# 2017MXP_board.net
KiCad netlist of a schematic drawn in EAGLE
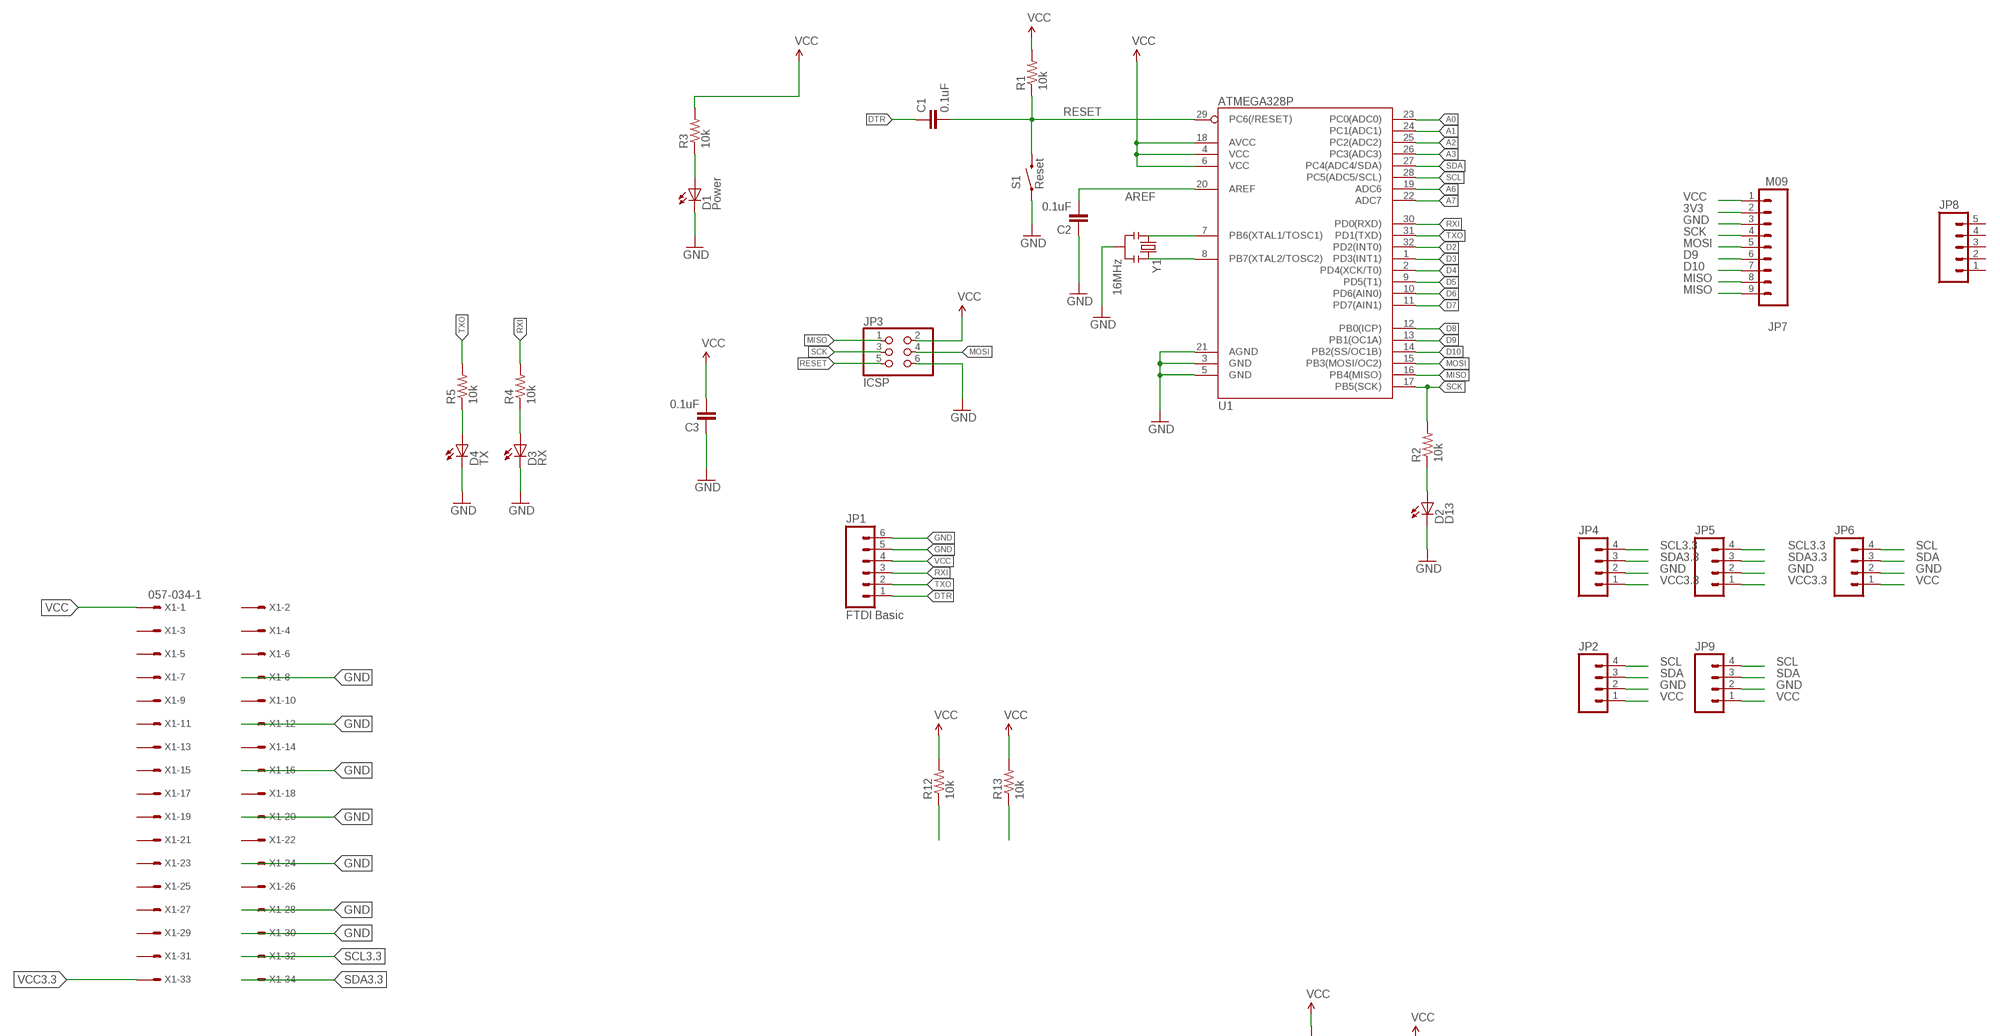
[diagram p0: schematic, sheet 1, part 1 of 2]
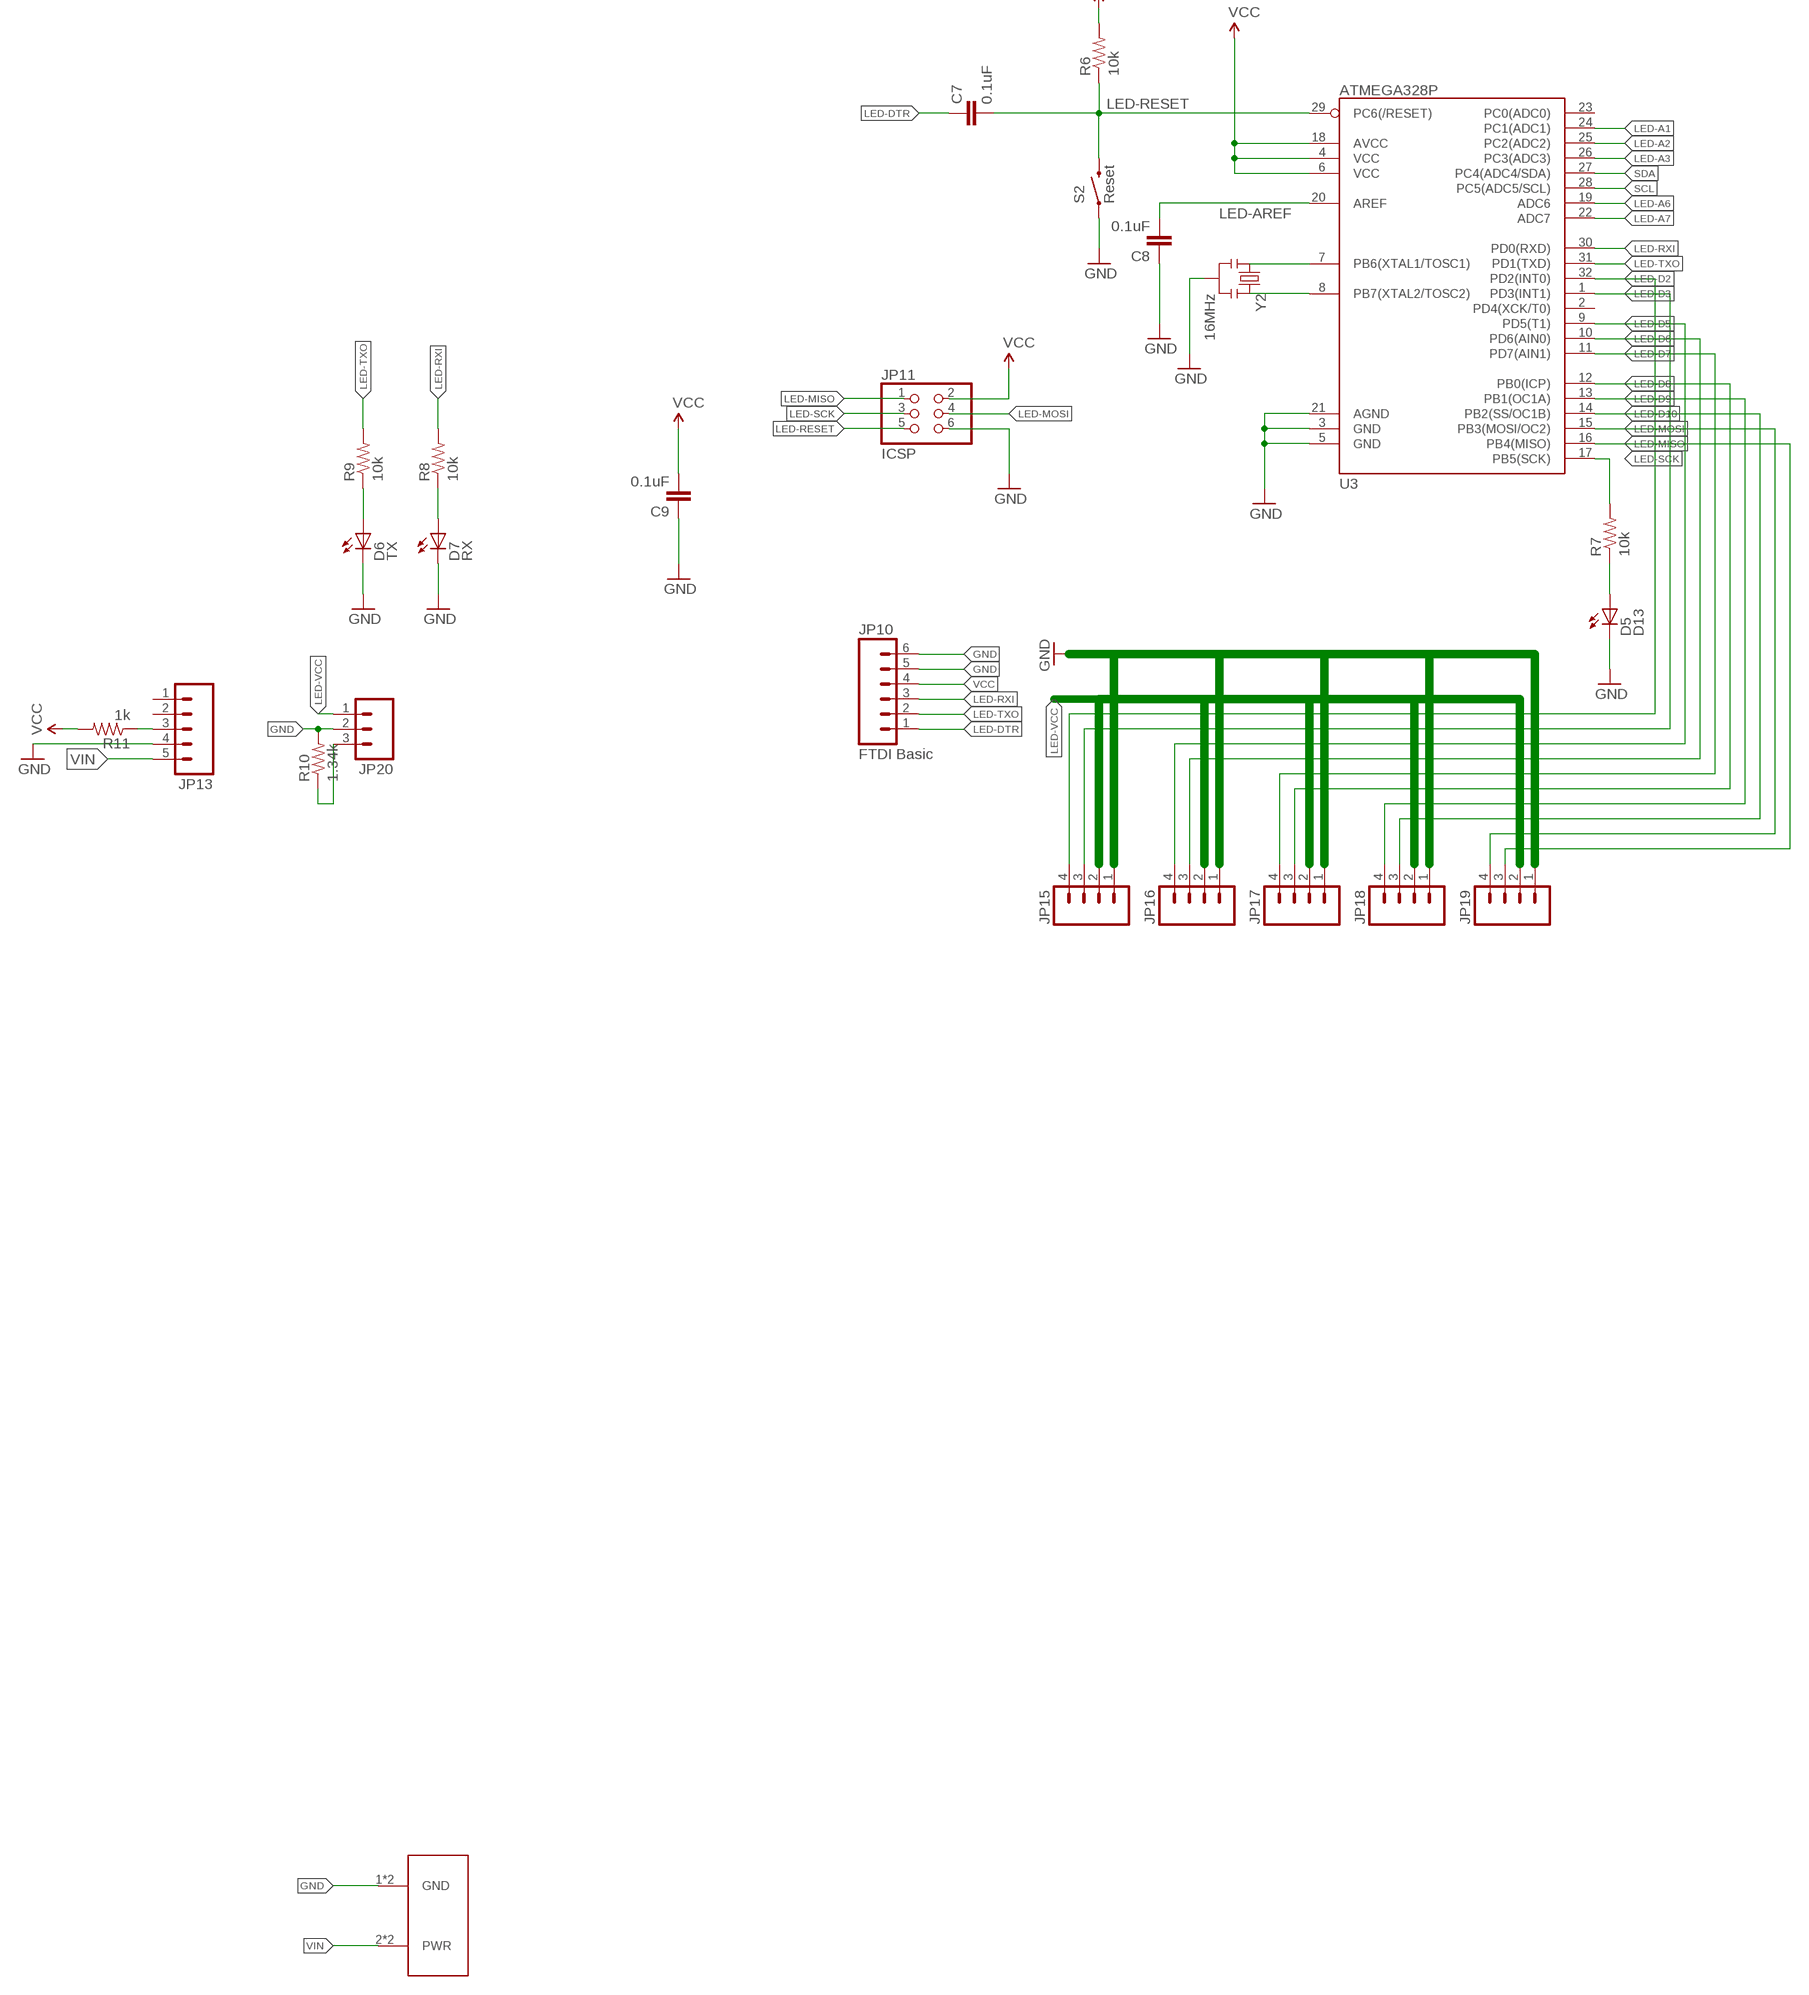
[diagram p1: schematic, sheet 1, part 2 of 2]

(export (version "E")
  (design (tool "Eeschema 10.0.6"))
  (components
    (comp (ref "C1")
      (value "0.1uF")
      (footprint "eagle-import:0603-CAP")
      (libsource (lib "eagle-import") (part "CAP0603-CAP"))
    )
    (comp (ref "C2")
      (value "0.1uF")
      (footprint "eagle-import:0603-CAP")
      (libsource (lib "eagle-import") (part "CAP0603-CAP"))
    )
    (comp (ref "C3")
      (value "0.1uF")
      (footprint "eagle-import:0603-CAP")
      (libsource (lib "eagle-import") (part "CAP0603-CAP"))
    )
    (comp (ref "C7")
      (value "0.1uF")
      (footprint "eagle-import:0603-CAP")
      (libsource (lib "eagle-import") (part "CAP0603-CAP"))
    )
    (comp (ref "C8")
      (value "0.1uF")
      (footprint "eagle-import:0603-CAP")
      (libsource (lib "eagle-import") (part "CAP0603-CAP"))
    )
    (comp (ref "C9")
      (value "0.1uF")
      (footprint "eagle-import:0603-CAP")
      (libsource (lib "eagle-import") (part "CAP0603-CAP"))
    )
    (comp (ref "D1")
      (value "Power")
      (footprint "eagle-import:LED-0603")
      (libsource (lib "eagle-import") (part "LED-RED0603"))
    )
    (comp (ref "D2")
      (value "D13")
      (footprint "eagle-import:LED-0603")
      (libsource (lib "eagle-import") (part "LED-RED0603"))
    )
    (comp (ref "D3")
      (value "RX")
      (footprint "eagle-import:LED-0603")
      (libsource (lib "eagle-import") (part "LED-GREEN0603"))
    )
    (comp (ref "D4")
      (value "TX")
      (footprint "eagle-import:LED-0603")
      (libsource (lib "eagle-import") (part "LED-RED0603"))
    )
    (comp (ref "D5")
      (value "D13")
      (footprint "eagle-import:LED-0603")
      (libsource (lib "eagle-import") (part "LED-RED0603"))
    )
    (comp (ref "D6")
      (value "TX")
      (footprint "eagle-import:LED-0603")
      (libsource (lib "eagle-import") (part "LED-RED0603"))
    )
    (comp (ref "D7")
      (value "RX")
      (footprint "eagle-import:LED-0603")
      (libsource (lib "eagle-import") (part "LED-GREEN0603"))
    )
    (comp (ref "JP1")
      (value "FTDI Basic")
      (footprint "eagle-import:1X06")
      (libsource (lib "eagle-import") (part "M06SIP"))
    )
    (comp (ref "JP2")
      (value "M04PTH")
      (footprint "eagle-import:1X04")
      (libsource (lib "eagle-import") (part "M04PTH"))
    )
    (comp (ref "JP3")
      (value "ICSP")
      (footprint "eagle-import:2X03")
      (libsource (lib "eagle-import") (part "PINHD-2X3"))
    )
    (comp (ref "JP4")
      (value "M04PTH")
      (footprint "eagle-import:1X04")
      (libsource (lib "eagle-import") (part "M04PTH"))
    )
    (comp (ref "JP5")
      (value "M04PTH")
      (footprint "eagle-import:1X04")
      (libsource (lib "eagle-import") (part "M04PTH"))
    )
    (comp (ref "JP6")
      (value "M04PTH")
      (footprint "eagle-import:1X04")
      (libsource (lib "eagle-import") (part "M04PTH"))
    )
    (comp (ref "JP7")
      (value "M09")
      (footprint "eagle-import:1X09")
      (libsource (lib "eagle-import") (part "M09"))
    )
    (comp (ref "JP8")
      (value "M05PTH")
      (footprint "eagle-import:1X05")
      (libsource (lib "eagle-import") (part "M05PTH"))
    )
    (comp (ref "JP9")
      (value "M04PTH")
      (footprint "eagle-import:1X04")
      (libsource (lib "eagle-import") (part "M04PTH"))
    )
    (comp (ref "JP10")
      (value "FTDI Basic")
      (footprint "eagle-import:1X06")
      (libsource (lib "eagle-import") (part "M06SIP"))
    )
    (comp (ref "JP11")
      (value "ICSP")
      (footprint "eagle-import:2X03")
      (libsource (lib "eagle-import") (part "PINHD-2X3"))
    )
    (comp (ref "JP13")
      (value "M05PTH")
      (footprint "eagle-import:1X05")
      (libsource (lib "eagle-import") (part "M05PTH"))
    )
    (comp (ref "JP15")
      (value "M04PTH")
      (footprint "eagle-import:1X04")
      (libsource (lib "eagle-import") (part "M04PTH"))
    )
    (comp (ref "JP16")
      (value "M04PTH")
      (footprint "eagle-import:1X04")
      (libsource (lib "eagle-import") (part "M04PTH"))
    )
    (comp (ref "JP17")
      (value "M04PTH")
      (footprint "eagle-import:1X04")
      (libsource (lib "eagle-import") (part "M04PTH"))
    )
    (comp (ref "JP18")
      (value "M04PTH")
      (footprint "eagle-import:1X04")
      (libsource (lib "eagle-import") (part "M04PTH"))
    )
    (comp (ref "JP19")
      (value "M04PTH")
      (footprint "eagle-import:1X04")
      (libsource (lib "eagle-import") (part "M04PTH"))
    )
    (comp (ref "JP20")
      (value "M03PTH")
      (footprint "eagle-import:1X03")
      (libsource (lib "eagle-import") (part "M03PTH"))
    )
    (comp (ref "R1")
      (value "10k")
      (footprint "eagle-import:0603-RES")
      (libsource (lib "eagle-import") (part "RESISTOR0603-RES"))
    )
    (comp (ref "R2")
      (value "10k")
      (footprint "eagle-import:0603-RES")
      (libsource (lib "eagle-import") (part "RESISTOR0603-RES"))
    )
    (comp (ref "R3")
      (value "10k")
      (footprint "eagle-import:0603-RES")
      (libsource (lib "eagle-import") (part "RESISTOR0603-RES"))
    )
    (comp (ref "R4")
      (value "10k")
      (footprint "eagle-import:0603-RES")
      (libsource (lib "eagle-import") (part "RESISTOR0603-RES"))
    )
    (comp (ref "R5")
      (value "10k")
      (footprint "eagle-import:0603-RES")
      (libsource (lib "eagle-import") (part "RESISTOR0603-RES"))
    )
    (comp (ref "R6")
      (value "10k")
      (footprint "eagle-import:0603-RES")
      (libsource (lib "eagle-import") (part "RESISTOR0603-RES"))
    )
    (comp (ref "R7")
      (value "10k")
      (footprint "eagle-import:0603-RES")
      (libsource (lib "eagle-import") (part "RESISTOR0603-RES"))
    )
    (comp (ref "R8")
      (value "10k")
      (footprint "eagle-import:0603-RES")
      (libsource (lib "eagle-import") (part "RESISTOR0603-RES"))
    )
    (comp (ref "R9")
      (value "10k")
      (footprint "eagle-import:0603-RES")
      (libsource (lib "eagle-import") (part "RESISTOR0603-RES"))
    )
    (comp (ref "R10")
      (value "1.34k")
      (footprint "eagle-import:AXIAL-0.3")
      (libsource (lib "eagle-import") (part "SparkFun-Resistors_RESISTORAXIAL-0.3"))
    )
    (comp (ref "R11")
      (value "1k")
      (footprint "eagle-import:AXIAL-0.3")
      (libsource (lib "eagle-import") (part "SparkFun-Resistors_RESISTORAXIAL-0.3"))
    )
    (comp (ref "R12")
      (value "10k")
      (footprint "eagle-import:0603-RES")
      (libsource (lib "eagle-import") (part "RESISTOR0603-RES"))
    )
    (comp (ref "R13")
      (value "10k")
      (footprint "eagle-import:0603-RES")
      (libsource (lib "eagle-import") (part "RESISTOR0603-RES"))
    )
    (comp (ref "S1")
      (value "Reset")
      (footprint "eagle-import:TACTILE_SWITCH_SMD")
      (libsource (lib "eagle-import") (part "SWITCH-MOMENTARY-2SMD"))
    )
    (comp (ref "S2")
      (value "Reset")
      (footprint "eagle-import:TACTILE_SWITCH_SMD")
      (libsource (lib "eagle-import") (part "SWITCH-MOMENTARY-2SMD"))
    )
    (comp (ref "U$2")
      (value "LSF-SMT")
      (footprint "eagle-import:LSF-SMT")
      (libsource (lib "eagle-import") (part "LSF-SMT"))
    )
    (comp (ref "U1")
      (value "ATMEGA328P")
      (footprint "eagle-import:TQFP32-08")
      (libsource (lib "eagle-import") (part "ATMEGA328_SMT"))
    )
    (comp (ref "U3")
      (value "ATMEGA328P")
      (footprint "eagle-import:TQFP32-08")
      (libsource (lib "eagle-import") (part "ATMEGA328_SMT"))
    )
    (comp (ref "X1")
      (value "057-034-1")
      (footprint "eagle-import:057-034-1")
      (libsource (lib "eagle-import") (part "057-034-1"))
    )
    (comp (ref "Y1")
      (value "16MHz")
      (footprint "eagle-import:RESONATOR-SMD")
      (libsource (lib "eagle-import") (part "RESONATOR16MHZ"))
    )
    (comp (ref "Y2")
      (value "16MHz")
      (footprint "eagle-import:RESONATOR-SMD")
      (libsource (lib "eagle-import") (part "RESONATOR16MHZ"))
    )
  )
  (nets
    (net (code "1") (name "/3V3") (class "Default")
      (node (ref "JP7") (pin "2") (pinfunction "2_2") (pintype "passive"))
    )
    (net (code "2") (name "/AREF") (class "Default")
      (node (ref "C2") (pin "2") (pinfunction "2_2") (pintype "passive"))
      (node (ref "U1") (pin "20") (pinfunction "AREF_20") (pintype "bidirectional"))
    )
    (net (code "3") (name "/LED-AREF") (class "Default")
      (node (ref "C8") (pin "2") (pinfunction "2_2") (pintype "passive"))
      (node (ref "U3") (pin "20") (pinfunction "AREF_20") (pintype "bidirectional"))
    )
    (net (code "4") (name "A0") (class "Default")
      (node (ref "U1") (pin "23") (pinfunction "PC0(ADC0)_23") (pintype "bidirectional"))
    )
    (net (code "5") (name "A1") (class "Default")
      (node (ref "U1") (pin "24") (pinfunction "PC1(ADC1)_24") (pintype "bidirectional"))
    )
    (net (code "6") (name "A2") (class "Default")
      (node (ref "U1") (pin "25") (pinfunction "PC2(ADC2)_25") (pintype "bidirectional"))
    )
    (net (code "7") (name "A3") (class "Default")
      (node (ref "U1") (pin "26") (pinfunction "PC3(ADC3)_26") (pintype "bidirectional"))
    )
    (net (code "8") (name "A6") (class "Default")
      (node (ref "U1") (pin "19") (pinfunction "ADC6_19") (pintype "bidirectional"))
    )
    (net (code "9") (name "A7") (class "Default")
      (node (ref "U1") (pin "22") (pinfunction "ADC7_22") (pintype "bidirectional"))
    )
    (net (code "10") (name "D2") (class "Default")
      (node (ref "U1") (pin "32") (pinfunction "PD2(INT0)_32") (pintype "bidirectional"))
    )
    (net (code "11") (name "D3") (class "Default")
      (node (ref "U1") (pin "1") (pinfunction "PD3(INT1)_1") (pintype "bidirectional"))
    )
    (net (code "12") (name "D4") (class "Default")
      (node (ref "U1") (pin "2") (pinfunction "PD4(XCK/T0)_2") (pintype "bidirectional"))
    )
    (net (code "13") (name "D5") (class "Default")
      (node (ref "U1") (pin "9") (pinfunction "PD5(T1)_9") (pintype "bidirectional"))
    )
    (net (code "14") (name "D6") (class "Default")
      (node (ref "U1") (pin "10") (pinfunction "PD6(AIN0)_10") (pintype "bidirectional"))
    )
    (net (code "15") (name "D7") (class "Default")
      (node (ref "U1") (pin "11") (pinfunction "PD7(AIN1)_11") (pintype "bidirectional"))
    )
    (net (code "16") (name "D8") (class "Default")
      (node (ref "U1") (pin "12") (pinfunction "PB0(ICP)_12") (pintype "bidirectional"))
    )
    (net (code "17") (name "D9") (class "Default")
      (node (ref "JP7") (pin "6") (pinfunction "6_6") (pintype "passive"))
      (node (ref "U1") (pin "13") (pinfunction "PB1(OC1A)_13") (pintype "bidirectional"))
    )
    (net (code "18") (name "D10") (class "Default")
      (node (ref "JP7") (pin "7") (pinfunction "7_7") (pintype "passive"))
      (node (ref "U1") (pin "14") (pinfunction "PB2(SS/OC1B)_14") (pintype "bidirectional"))
    )
    (net (code "19") (name "DTR") (class "Default")
      (node (ref "C1") (pin "1") (pinfunction "1_1") (pintype "passive"))
      (node (ref "JP1") (pin "1") (pinfunction "1_1") (pintype "passive"))
    )
    (net (code "20") (name "GND") (class "Default")
      (node (ref "C2") (pin "1") (pinfunction "1_1") (pintype "passive"))
      (node (ref "C3") (pin "1") (pinfunction "1_1") (pintype "passive"))
      (node (ref "C8") (pin "1") (pinfunction "1_1") (pintype "passive"))
      (node (ref "C9") (pin "1") (pinfunction "1_1") (pintype "passive"))
      (node (ref "D1") (pin "C") (pinfunction "C_C") (pintype "passive"))
      (node (ref "D2") (pin "C") (pinfunction "C_C") (pintype "passive"))
      (node (ref "D3") (pin "C") (pinfunction "C_C") (pintype "passive"))
      (node (ref "D4") (pin "C") (pinfunction "C_C") (pintype "passive"))
      (node (ref "D5") (pin "C") (pinfunction "C_C") (pintype "passive"))
      (node (ref "D6") (pin "C") (pinfunction "C_C") (pintype "passive"))
      (node (ref "D7") (pin "C") (pinfunction "C_C") (pintype "passive"))
      (node (ref "JP1") (pin "5") (pinfunction "5_5") (pintype "passive"))
      (node (ref "JP1") (pin "6") (pinfunction "6_6") (pintype "passive"))
      (node (ref "JP10") (pin "5") (pinfunction "5_5") (pintype "passive"))
      (node (ref "JP10") (pin "6") (pinfunction "6_6") (pintype "passive"))
      (node (ref "JP11") (pin "6") (pinfunction "6_6") (pintype "passive"))
      (node (ref "JP13") (pin "4") (pinfunction "4_4") (pintype "passive"))
      (node (ref "JP15") (pin "1") (pinfunction "1_1") (pintype "passive"))
      (node (ref "JP16") (pin "1") (pinfunction "1_1") (pintype "passive"))
      (node (ref "JP17") (pin "1") (pinfunction "1_1") (pintype "passive"))
      (node (ref "JP18") (pin "1") (pinfunction "1_1") (pintype "passive"))
      (node (ref "JP19") (pin "1") (pinfunction "1_1") (pintype "passive"))
      (node (ref "JP2") (pin "2") (pinfunction "2_2") (pintype "passive"))
      (node (ref "JP20") (pin "2") (pinfunction "2_2") (pintype "passive"))
      (node (ref "JP3") (pin "6") (pinfunction "6_6") (pintype "passive"))
      (node (ref "JP4") (pin "2") (pinfunction "2_2") (pintype "passive"))
      (node (ref "JP5") (pin "2") (pinfunction "2_2") (pintype "passive"))
      (node (ref "JP6") (pin "2") (pinfunction "2_2") (pintype "passive"))
      (node (ref "JP7") (pin "3") (pinfunction "3_3") (pintype "passive"))
      (node (ref "JP9") (pin "2") (pinfunction "2_2") (pintype "passive"))
      (node (ref "R10") (pin "P$2") (pinfunction "2_P$2") (pintype "passive"))
      (node (ref "S1") (pin "1") (pinfunction "1_1") (pintype "passive"))
      (node (ref "S2") (pin "1") (pinfunction "1_1") (pintype "passive"))
      (node (ref "U$2") (pin "1") (pinfunction "GND_1") (pintype "bidirectional"))
      (node (ref "U$2") (pin "1-2") (pinfunction "GND_1-2") (pintype "bidirectional"))
      (node (ref "U1") (pin "21") (pinfunction "AGND_21") (pintype "bidirectional"))
      (node (ref "U1") (pin "3") (pinfunction "GND_3") (pintype "bidirectional"))
      (node (ref "U1") (pin "5") (pinfunction "GND_5") (pintype "bidirectional"))
      (node (ref "U3") (pin "21") (pinfunction "AGND_21") (pintype "bidirectional"))
      (node (ref "U3") (pin "3") (pinfunction "GND_3") (pintype "bidirectional"))
      (node (ref "U3") (pin "5") (pinfunction "GND_5") (pintype "bidirectional"))
      (node (ref "X1") (pin "12") (pinfunction "S_12") (pintype "passive"))
      (node (ref "X1") (pin "16") (pinfunction "S_16") (pintype "passive"))
      (node (ref "X1") (pin "20") (pinfunction "S_20") (pintype "passive"))
      (node (ref "X1") (pin "24") (pinfunction "S_24") (pintype "passive"))
      (node (ref "X1") (pin "28") (pinfunction "S_28") (pintype "passive"))
      (node (ref "X1") (pin "30") (pinfunction "S_30") (pintype "passive"))
      (node (ref "X1") (pin "8") (pinfunction "S_8") (pintype "passive"))
      (node (ref "Y1") (pin "2") (pinfunction "2_2") (pintype "passive"))
      (node (ref "Y2") (pin "2") (pinfunction "2_2") (pintype "passive"))
    )
    (net (code "21") (name "LED-A1") (class "Default")
      (node (ref "U3") (pin "24") (pinfunction "PC1(ADC1)_24") (pintype "bidirectional"))
    )
    (net (code "22") (name "LED-A2") (class "Default")
      (node (ref "U3") (pin "25") (pinfunction "PC2(ADC2)_25") (pintype "bidirectional"))
    )
    (net (code "23") (name "LED-A3") (class "Default")
      (node (ref "U3") (pin "26") (pinfunction "PC3(ADC3)_26") (pintype "bidirectional"))
    )
    (net (code "24") (name "LED-A6") (class "Default")
      (node (ref "U3") (pin "19") (pinfunction "ADC6_19") (pintype "bidirectional"))
    )
    (net (code "25") (name "LED-A7") (class "Default")
      (node (ref "U3") (pin "22") (pinfunction "ADC7_22") (pintype "bidirectional"))
    )
    (net (code "26") (name "LED-D2") (class "Default")
      (node (ref "JP15") (pin "4") (pinfunction "4_4") (pintype "passive"))
      (node (ref "U3") (pin "32") (pinfunction "PD2(INT0)_32") (pintype "bidirectional"))
    )
    (net (code "27") (name "LED-D3") (class "Default")
      (node (ref "JP15") (pin "3") (pinfunction "3_3") (pintype "passive"))
      (node (ref "U3") (pin "1") (pinfunction "PD3(INT1)_1") (pintype "bidirectional"))
    )
    (net (code "28") (name "LED-D5") (class "Default")
      (node (ref "JP16") (pin "4") (pinfunction "4_4") (pintype "passive"))
      (node (ref "U3") (pin "9") (pinfunction "PD5(T1)_9") (pintype "bidirectional"))
    )
    (net (code "29") (name "LED-D6") (class "Default")
      (node (ref "JP16") (pin "3") (pinfunction "3_3") (pintype "passive"))
      (node (ref "U3") (pin "10") (pinfunction "PD6(AIN0)_10") (pintype "bidirectional"))
    )
    (net (code "30") (name "LED-D7") (class "Default")
      (node (ref "JP17") (pin "4") (pinfunction "4_4") (pintype "passive"))
      (node (ref "U3") (pin "11") (pinfunction "PD7(AIN1)_11") (pintype "bidirectional"))
    )
    (net (code "31") (name "LED-D8") (class "Default")
      (node (ref "JP17") (pin "3") (pinfunction "3_3") (pintype "passive"))
      (node (ref "U3") (pin "12") (pinfunction "PB0(ICP)_12") (pintype "bidirectional"))
    )
    (net (code "32") (name "LED-D9") (class "Default")
      (node (ref "JP18") (pin "4") (pinfunction "4_4") (pintype "passive"))
      (node (ref "U3") (pin "13") (pinfunction "PB1(OC1A)_13") (pintype "bidirectional"))
    )
    (net (code "33") (name "LED-D10") (class "Default")
      (node (ref "JP18") (pin "3") (pinfunction "3_3") (pintype "passive"))
      (node (ref "U3") (pin "14") (pinfunction "PB2(SS/OC1B)_14") (pintype "bidirectional"))
    )
    (net (code "34") (name "LED-DTR") (class "Default")
      (node (ref "C7") (pin "1") (pinfunction "1_1") (pintype "passive"))
      (node (ref "JP10") (pin "1") (pinfunction "1_1") (pintype "passive"))
    )
    (net (code "35") (name "LED-MISO") (class "Default")
      (node (ref "JP11") (pin "1") (pinfunction "1_1") (pintype "passive"))
      (node (ref "JP19") (pin "3") (pinfunction "3_3") (pintype "passive"))
      (node (ref "U3") (pin "16") (pinfunction "PB4(MISO)_16") (pintype "bidirectional"))
    )
    (net (code "36") (name "LED-MOSI") (class "Default")
      (node (ref "JP11") (pin "4") (pinfunction "4_4") (pintype "passive"))
      (node (ref "JP19") (pin "4") (pinfunction "4_4") (pintype "passive"))
      (node (ref "U3") (pin "15") (pinfunction "PB3(MOSI/OC2)_15") (pintype "bidirectional"))
    )
    (net (code "37") (name "LED-RESET") (class "Default")
      (node (ref "C7") (pin "2") (pinfunction "2_2") (pintype "passive"))
      (node (ref "JP11") (pin "5") (pinfunction "5_5") (pintype "passive"))
      (node (ref "R6") (pin "1") (pinfunction "1_1") (pintype "passive"))
      (node (ref "S2") (pin "3") (pinfunction "2_3") (pintype "passive"))
      (node (ref "U3") (pin "29") (pinfunction "PC6(/RESET)_29") (pintype "bidirectional"))
    )
    (net (code "38") (name "LED-RXI") (class "Default")
      (node (ref "JP10") (pin "3") (pinfunction "3_3") (pintype "passive"))
      (node (ref "R8") (pin "2") (pinfunction "2_2") (pintype "passive"))
      (node (ref "U3") (pin "30") (pinfunction "PD0(RXD)_30") (pintype "bidirectional"))
    )
    (net (code "39") (name "LED-SCK") (class "Default")
      (node (ref "JP11") (pin "3") (pinfunction "3_3") (pintype "passive"))
      (node (ref "R7") (pin "2") (pinfunction "2_2") (pintype "passive"))
      (node (ref "U3") (pin "17") (pinfunction "PB5(SCK)_17") (pintype "bidirectional"))
    )
    (net (code "40") (name "LED-TXO") (class "Default")
      (node (ref "JP10") (pin "2") (pinfunction "2_2") (pintype "passive"))
      (node (ref "R9") (pin "2") (pinfunction "2_2") (pintype "passive"))
      (node (ref "U3") (pin "31") (pinfunction "PD1(TXD)_31") (pintype "bidirectional"))
    )
    (net (code "41") (name "LED-VCC") (class "Default")
      (node (ref "JP15") (pin "2") (pinfunction "2_2") (pintype "passive"))
      (node (ref "JP16") (pin "2") (pinfunction "2_2") (pintype "passive"))
      (node (ref "JP17") (pin "2") (pinfunction "2_2") (pintype "passive"))
      (node (ref "JP18") (pin "2") (pinfunction "2_2") (pintype "passive"))
      (node (ref "JP19") (pin "2") (pinfunction "2_2") (pintype "passive"))
      (node (ref "JP20") (pin "1") (pinfunction "1_1") (pintype "passive"))
    )
    (net (code "42") (name "MISO") (class "Default")
      (node (ref "JP3") (pin "1") (pinfunction "1_1") (pintype "passive"))
      (node (ref "JP7") (pin "8") (pinfunction "8_8") (pintype "passive"))
      (node (ref "JP7") (pin "9") (pinfunction "9_9") (pintype "passive"))
      (node (ref "U1") (pin "16") (pinfunction "PB4(MISO)_16") (pintype "bidirectional"))
    )
    (net (code "43") (name "MOSI") (class "Default")
      (node (ref "JP3") (pin "4") (pinfunction "4_4") (pintype "passive"))
      (node (ref "JP7") (pin "5") (pinfunction "5_5") (pintype "passive"))
      (node (ref "U1") (pin "15") (pinfunction "PB3(MOSI/OC2)_15") (pintype "bidirectional"))
    )
    (net (code "44") (name "Net-(D1-PadA)") (class "Default")
      (node (ref "D1") (pin "A") (pinfunction "A_A") (pintype "passive"))
      (node (ref "R3") (pin "1") (pinfunction "1_1") (pintype "passive"))
    )
    (net (code "45") (name "Net-(D2-PadA)") (class "Default")
      (node (ref "D2") (pin "A") (pinfunction "A_A") (pintype "passive"))
      (node (ref "R2") (pin "1") (pinfunction "1_1") (pintype "passive"))
    )
    (net (code "46") (name "Net-(D3-PadA)") (class "Default")
      (node (ref "D3") (pin "A") (pinfunction "A_A") (pintype "passive"))
      (node (ref "R4") (pin "1") (pinfunction "1_1") (pintype "passive"))
    )
    (net (code "47") (name "Net-(D4-PadA)") (class "Default")
      (node (ref "D4") (pin "A") (pinfunction "A_A") (pintype "passive"))
      (node (ref "R5") (pin "1") (pinfunction "1_1") (pintype "passive"))
    )
    (net (code "48") (name "Net-(D5-PadA)") (class "Default")
      (node (ref "D5") (pin "A") (pinfunction "A_A") (pintype "passive"))
      (node (ref "R7") (pin "1") (pinfunction "1_1") (pintype "passive"))
    )
    (net (code "49") (name "Net-(D6-PadA)") (class "Default")
      (node (ref "D6") (pin "A") (pinfunction "A_A") (pintype "passive"))
      (node (ref "R9") (pin "1") (pinfunction "1_1") (pintype "passive"))
    )
    (net (code "50") (name "Net-(D7-PadA)") (class "Default")
      (node (ref "D7") (pin "A") (pinfunction "A_A") (pintype "passive"))
      (node (ref "R8") (pin "1") (pinfunction "1_1") (pintype "passive"))
    )
    (net (code "51") (name "Net-(R10-1)") (class "Default")
      (node (ref "JP20") (pin "3") (pinfunction "3_3") (pintype "passive"))
      (node (ref "R10") (pin "P$1") (pinfunction "1_P$1") (pintype "passive"))
    )
    (net (code "52") (name "Net-(R11-1)") (class "Default")
      (node (ref "JP13") (pin "3") (pinfunction "3_3") (pintype "passive"))
      (node (ref "R11") (pin "P$1") (pinfunction "1_P$1") (pintype "passive"))
    )
    (net (code "53") (name "Net-(U1-PB6(XTAL1{slash}TOSC1))") (class "Default")
      (node (ref "U1") (pin "7") (pinfunction "PB6(XTAL1/TOSC1)_7") (pintype "bidirectional"))
      (node (ref "Y1") (pin "1") (pinfunction "1_1") (pintype "passive"))
    )
    (net (code "54") (name "Net-(U1-PB7(XTAL2{slash}TOSC2))") (class "Default")
      (node (ref "U1") (pin "8") (pinfunction "PB7(XTAL2/TOSC2)_8") (pintype "bidirectional"))
      (node (ref "Y1") (pin "3") (pinfunction "3_3") (pintype "passive"))
    )
    (net (code "55") (name "Net-(U3-PB6(XTAL1{slash}TOSC1))") (class "Default")
      (node (ref "U3") (pin "7") (pinfunction "PB6(XTAL1/TOSC1)_7") (pintype "bidirectional"))
      (node (ref "Y2") (pin "1") (pinfunction "1_1") (pintype "passive"))
    )
    (net (code "56") (name "Net-(U3-PB7(XTAL2{slash}TOSC2))") (class "Default")
      (node (ref "U3") (pin "8") (pinfunction "PB7(XTAL2/TOSC2)_8") (pintype "bidirectional"))
      (node (ref "Y2") (pin "3") (pinfunction "3_3") (pintype "passive"))
    )
    (net (code "57") (name "RESET") (class "Default")
      (node (ref "C1") (pin "2") (pinfunction "2_2") (pintype "passive"))
      (node (ref "JP3") (pin "5") (pinfunction "5_5") (pintype "passive"))
      (node (ref "R1") (pin "1") (pinfunction "1_1") (pintype "passive"))
      (node (ref "S1") (pin "3") (pinfunction "2_3") (pintype "passive"))
      (node (ref "U1") (pin "29") (pinfunction "PC6(/RESET)_29") (pintype "bidirectional"))
    )
    (net (code "58") (name "RXI") (class "Default")
      (node (ref "JP1") (pin "3") (pinfunction "3_3") (pintype "passive"))
      (node (ref "R4") (pin "2") (pinfunction "2_2") (pintype "passive"))
      (node (ref "U1") (pin "30") (pinfunction "PD0(RXD)_30") (pintype "bidirectional"))
    )
    (net (code "59") (name "SCK") (class "Default")
      (node (ref "JP3") (pin "3") (pinfunction "3_3") (pintype "passive"))
      (node (ref "JP7") (pin "4") (pinfunction "4_4") (pintype "passive"))
      (node (ref "R2") (pin "2") (pinfunction "2_2") (pintype "passive"))
      (node (ref "U1") (pin "17") (pinfunction "PB5(SCK)_17") (pintype "bidirectional"))
    )
    (net (code "60") (name "SCL") (class "Default")
      (node (ref "JP2") (pin "4") (pinfunction "4_4") (pintype "passive"))
      (node (ref "JP6") (pin "4") (pinfunction "4_4") (pintype "passive"))
      (node (ref "JP9") (pin "4") (pinfunction "4_4") (pintype "passive"))
      (node (ref "R13") (pin "1") (pinfunction "1_1") (pintype "passive"))
      (node (ref "U1") (pin "28") (pinfunction "PC5(ADC5/SCL)_28") (pintype "bidirectional"))
      (node (ref "U3") (pin "28") (pinfunction "PC5(ADC5/SCL)_28") (pintype "bidirectional"))
    )
    (net (code "61") (name "SCL3.3") (class "Default")
      (node (ref "JP4") (pin "4") (pinfunction "4_4") (pintype "passive"))
      (node (ref "JP5") (pin "4") (pinfunction "4_4") (pintype "passive"))
      (node (ref "X1") (pin "32") (pinfunction "S_32") (pintype "passive"))
    )
    (net (code "62") (name "SDA") (class "Default")
      (node (ref "JP2") (pin "3") (pinfunction "3_3") (pintype "passive"))
      (node (ref "JP6") (pin "3") (pinfunction "3_3") (pintype "passive"))
      (node (ref "JP9") (pin "3") (pinfunction "3_3") (pintype "passive"))
      (node (ref "R12") (pin "1") (pinfunction "1_1") (pintype "passive"))
      (node (ref "U1") (pin "27") (pinfunction "PC4(ADC4/SDA)_27") (pintype "bidirectional"))
      (node (ref "U3") (pin "27") (pinfunction "PC4(ADC4/SDA)_27") (pintype "bidirectional"))
    )
    (net (code "63") (name "SDA3.3") (class "Default")
      (node (ref "JP4") (pin "3") (pinfunction "3_3") (pintype "passive"))
      (node (ref "JP5") (pin "3") (pinfunction "3_3") (pintype "passive"))
      (node (ref "X1") (pin "34") (pinfunction "S_34") (pintype "passive"))
    )
    (net (code "64") (name "TXO") (class "Default")
      (node (ref "JP1") (pin "2") (pinfunction "2_2") (pintype "passive"))
      (node (ref "R5") (pin "2") (pinfunction "2_2") (pintype "passive"))
      (node (ref "U1") (pin "31") (pinfunction "PD1(TXD)_31") (pintype "bidirectional"))
    )
    (net (code "65") (name "VCC") (class "Default")
      (node (ref "C3") (pin "2") (pinfunction "2_2") (pintype "passive"))
      (node (ref "C9") (pin "2") (pinfunction "2_2") (pintype "passive"))
      (node (ref "JP1") (pin "4") (pinfunction "4_4") (pintype "passive"))
      (node (ref "JP10") (pin "4") (pinfunction "4_4") (pintype "passive"))
      (node (ref "JP11") (pin "2") (pinfunction "2_2") (pintype "passive"))
      (node (ref "JP2") (pin "1") (pinfunction "1_1") (pintype "passive"))
      (node (ref "JP3") (pin "2") (pinfunction "2_2") (pintype "passive"))
      (node (ref "JP6") (pin "1") (pinfunction "1_1") (pintype "passive"))
      (node (ref "JP7") (pin "1") (pinfunction "1_1") (pintype "passive"))
      (node (ref "JP9") (pin "1") (pinfunction "1_1") (pintype "passive"))
      (node (ref "R1") (pin "2") (pinfunction "2_2") (pintype "passive"))
      (node (ref "R11") (pin "P$2") (pinfunction "2_P$2") (pintype "passive"))
      (node (ref "R12") (pin "2") (pinfunction "2_2") (pintype "passive"))
      (node (ref "R13") (pin "2") (pinfunction "2_2") (pintype "passive"))
      (node (ref "R3") (pin "2") (pinfunction "2_2") (pintype "passive"))
      (node (ref "R6") (pin "2") (pinfunction "2_2") (pintype "passive"))
      (node (ref "U1") (pin "18") (pinfunction "AVCC_18") (pintype "bidirectional"))
      (node (ref "U1") (pin "4") (pinfunction "VCC_4") (pintype "bidirectional"))
      (node (ref "U1") (pin "6") (pinfunction "VCC_6") (pintype "bidirectional"))
      (node (ref "U3") (pin "18") (pinfunction "AVCC_18") (pintype "bidirectional"))
      (node (ref "U3") (pin "4") (pinfunction "VCC_4") (pintype "bidirectional"))
      (node (ref "U3") (pin "6") (pinfunction "VCC_6") (pintype "bidirectional"))
      (node (ref "X1") (pin "1") (pinfunction "S_1") (pintype "passive"))
    )
    (net (code "66") (name "VCC3.3") (class "Default")
      (node (ref "JP4") (pin "1") (pinfunction "1_1") (pintype "passive"))
      (node (ref "JP5") (pin "1") (pinfunction "1_1") (pintype "passive"))
      (node (ref "X1") (pin "33") (pinfunction "S_33") (pintype "passive"))
    )
    (net (code "67") (name "VIN") (class "Default")
      (node (ref "JP13") (pin "5") (pinfunction "5_5") (pintype "passive"))
      (node (ref "U$2") (pin "2") (pinfunction "PWR_2") (pintype "bidirectional"))
      (node (ref "U$2") (pin "2-2") (pinfunction "PWR_2-2") (pintype "bidirectional"))
    )
    (net (code "68") (name "unconnected-(JP8-Pad1)") (class "Default")
      (node (ref "JP8") (pin "1") (pinfunction "1_1") (pintype "passive"))
    )
    (net (code "69") (name "unconnected-(JP8-Pad2)") (class "Default")
      (node (ref "JP8") (pin "2") (pinfunction "2_2") (pintype "passive"))
    )
    (net (code "70") (name "unconnected-(JP8-Pad3)") (class "Default")
      (node (ref "JP8") (pin "3") (pinfunction "3_3") (pintype "passive"))
    )
    (net (code "71") (name "unconnected-(JP8-Pad4)") (class "Default")
      (node (ref "JP8") (pin "4") (pinfunction "4_4") (pintype "passive"))
    )
    (net (code "72") (name "unconnected-(JP8-Pad5)") (class "Default")
      (node (ref "JP8") (pin "5") (pinfunction "5_5") (pintype "passive"))
    )
    (net (code "73") (name "unconnected-(JP13-Pad1)") (class "Default")
      (node (ref "JP13") (pin "1") (pinfunction "1_1") (pintype "passive"))
    )
    (net (code "74") (name "unconnected-(JP13-Pad2)") (class "Default")
      (node (ref "JP13") (pin "2") (pinfunction "2_2") (pintype "passive"))
    )
    (net (code "75") (name "unconnected-(U3-PC0(ADC0)-Pad23)") (class "Default")
      (node (ref "U3") (pin "23") (pinfunction "PC0(ADC0)_23") (pintype "bidirectional"))
    )
    (net (code "76") (name "unconnected-(U3-PD4(XCK{slash}T0)-Pad2)") (class "Default")
      (node (ref "U3") (pin "2") (pinfunction "PD4(XCK/T0)_2") (pintype "bidirectional"))
    )
    (net (code "77") (name "unconnected-(X1AC-S-Pad4)") (class "Default")
      (node (ref "X1") (pin "4") (pinfunction "S_4") (pintype "passive"))
    )
    (net (code "78") (name "unconnected-(X1AD-S-Pad5)") (class "Default")
      (node (ref "X1") (pin "5") (pinfunction "S_5") (pintype "passive"))
    )
    (net (code "79") (name "unconnected-(X1AE-S-Pad6)") (class "Default")
      (node (ref "X1") (pin "6") (pinfunction "S_6") (pintype "passive"))
    )
    (net (code "80") (name "unconnected-(X1AF-S-Pad7)") (class "Default")
      (node (ref "X1") (pin "7") (pinfunction "S_7") (pintype "passive"))
    )
    (net (code "81") (name "unconnected-(X1AH-S-Pad9)") (class "Default")
      (node (ref "X1") (pin "9") (pinfunction "S_9") (pintype "passive"))
    )
    (net (code "82") (name "unconnected-(X1B-S-Pad10)") (class "Default")
      (node (ref "X1") (pin "10") (pinfunction "S_10") (pintype "passive"))
    )
    (net (code "83") (name "unconnected-(X1C-S-Pad11)") (class "Default")
      (node (ref "X1") (pin "11") (pinfunction "S_11") (pintype "passive"))
    )
    (net (code "84") (name "unconnected-(X1E-S-Pad13)") (class "Default")
      (node (ref "X1") (pin "13") (pinfunction "S_13") (pintype "passive"))
    )
    (net (code "85") (name "unconnected-(X1F-S-Pad14)") (class "Default")
      (node (ref "X1") (pin "14") (pinfunction "S_14") (pintype "passive"))
    )
    (net (code "86") (name "unconnected-(X1G-S-Pad15)") (class "Default")
      (node (ref "X1") (pin "15") (pinfunction "S_15") (pintype "passive"))
    )
    (net (code "87") (name "unconnected-(X1I-S-Pad17)") (class "Default")
      (node (ref "X1") (pin "17") (pinfunction "S_17") (pintype "passive"))
    )
    (net (code "88") (name "unconnected-(X1J-S-Pad18)") (class "Default")
      (node (ref "X1") (pin "18") (pinfunction "S_18") (pintype "passive"))
    )
    (net (code "89") (name "unconnected-(X1K-S-Pad19)") (class "Default")
      (node (ref "X1") (pin "19") (pinfunction "S_19") (pintype "passive"))
    )
    (net (code "90") (name "unconnected-(X1L-S-Pad2)") (class "Default")
      (node (ref "X1") (pin "2") (pinfunction "S_2") (pintype "passive"))
    )
    (net (code "91") (name "unconnected-(X1N-S-Pad21)") (class "Default")
      (node (ref "X1") (pin "21") (pinfunction "S_21") (pintype "passive"))
    )
    (net (code "92") (name "unconnected-(X1O-S-Pad22)") (class "Default")
      (node (ref "X1") (pin "22") (pinfunction "S_22") (pintype "passive"))
    )
    (net (code "93") (name "unconnected-(X1P-S-Pad23)") (class "Default")
      (node (ref "X1") (pin "23") (pinfunction "S_23") (pintype "passive"))
    )
    (net (code "94") (name "unconnected-(X1R-S-Pad25)") (class "Default")
      (node (ref "X1") (pin "25") (pinfunction "S_25") (pintype "passive"))
    )
    (net (code "95") (name "unconnected-(X1S-S-Pad26)") (class "Default")
      (node (ref "X1") (pin "26") (pinfunction "S_26") (pintype "passive"))
    )
    (net (code "96") (name "unconnected-(X1T-S-Pad27)") (class "Default")
      (node (ref "X1") (pin "27") (pinfunction "S_27") (pintype "passive"))
    )
    (net (code "97") (name "unconnected-(X1V-S-Pad29)") (class "Default")
      (node (ref "X1") (pin "29") (pinfunction "S_29") (pintype "passive"))
    )
    (net (code "98") (name "unconnected-(X1W-S-Pad3)") (class "Default")
      (node (ref "X1") (pin "3") (pinfunction "S_3") (pintype "passive"))
    )
    (net (code "99") (name "unconnected-(X1Y-S-Pad31)") (class "Default")
      (node (ref "X1") (pin "31") (pinfunction "S_31") (pintype "passive"))
    )
  )
)
